# 4_-_DRIVERS.net
KiCad netlist of a schematic drawn in Altium Designer
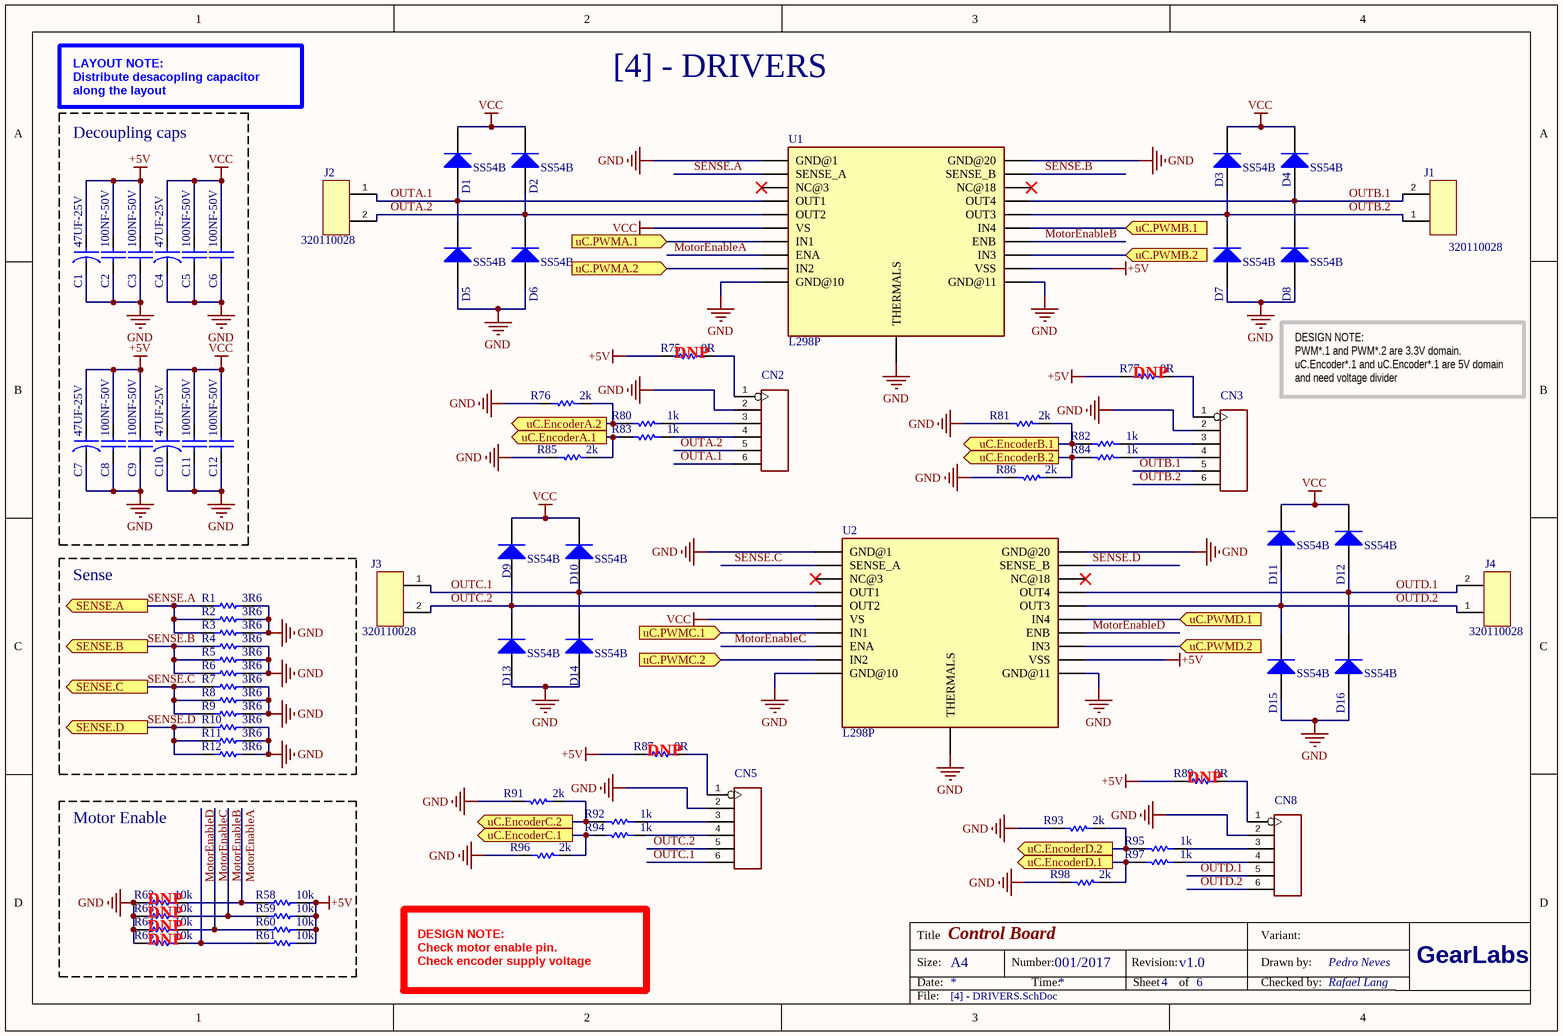
[diagram p0: [4] - DRIVERS.SchDoc]

(export (version "E")
  (design (tool "Eeschema 10.0.6"))
  (components
    (comp (ref "C1")
      (value "47UF-25V")
      (footprint "ELECTRO-SMD-C-6MM")
      (fields (field (name "MPN") "CS1E470M-CRE54") (field (name "Comment") "302030059"))
      (libsource (lib "Seeed-Capacitor") (part "ALUMINUM-SMD-47UF-25V(D6.3-H5.3MM)"))
    )
    (comp (ref "C2")
      (value "100NF-50V")
      (footprint "C0603")
      (fields (field (name "MPN") "CC0603KRX7R9BB104") (field (name "Comment") "302010138"))
      (libsource (lib "Seeed-Capacitor") (part "CERAMIC-100NF-50V-10%-X7R(0603)"))
    )
    (comp (ref "C3")
      (value "100NF-50V")
      (footprint "C0603")
      (fields (field (name "MPN") "CC0603KRX7R9BB104") (field (name "Comment") "302010138"))
      (libsource (lib "Seeed-Capacitor") (part "CERAMIC-100NF-50V-10%-X7R(0603)"))
    )
    (comp (ref "C4")
      (value "47UF-25V")
      (footprint "ELECTRO-SMD-C-6MM")
      (fields (field (name "MPN") "CS1E470M-CRE54") (field (name "Comment") "302030059"))
      (libsource (lib "Seeed-Capacitor") (part "ALUMINUM-SMD-47UF-25V(D6.3-H5.3MM)"))
    )
    (comp (ref "C5")
      (value "100NF-50V")
      (footprint "C0603")
      (fields (field (name "MPN") "CC0603KRX7R9BB104") (field (name "Comment") "302010138"))
      (libsource (lib "Seeed-Capacitor") (part "CERAMIC-100NF-50V-10%-X7R(0603)"))
    )
    (comp (ref "C6")
      (value "100NF-50V")
      (footprint "C0603")
      (fields (field (name "MPN") "CC0603KRX7R9BB104") (field (name "Comment") "302010138"))
      (libsource (lib "Seeed-Capacitor") (part "CERAMIC-100NF-50V-10%-X7R(0603)"))
    )
    (comp (ref "C7")
      (value "47UF-25V")
      (footprint "ELECTRO-SMD-C-6MM")
      (fields (field (name "MPN") "CS1E470M-CRE54") (field (name "Comment") "302030059"))
      (libsource (lib "Seeed-Capacitor") (part "ALUMINUM-SMD-47UF-25V(D6.3-H5.3MM)"))
    )
    (comp (ref "C8")
      (value "100NF-50V")
      (footprint "C0603")
      (fields (field (name "MPN") "CC0603KRX7R9BB104") (field (name "Comment") "302010138"))
      (libsource (lib "Seeed-Capacitor") (part "CERAMIC-100NF-50V-10%-X7R(0603)"))
    )
    (comp (ref "C9")
      (value "100NF-50V")
      (footprint "C0603")
      (fields (field (name "MPN") "CC0603KRX7R9BB104") (field (name "Comment") "302010138"))
      (libsource (lib "Seeed-Capacitor") (part "CERAMIC-100NF-50V-10%-X7R(0603)"))
    )
    (comp (ref "C10")
      (value "47UF-25V")
      (footprint "ELECTRO-SMD-C-6MM")
      (fields (field (name "MPN") "CS1E470M-CRE54") (field (name "Comment") "302030059"))
      (libsource (lib "Seeed-Capacitor") (part "ALUMINUM-SMD-47UF-25V(D6.3-H5.3MM)"))
    )
    (comp (ref "C11")
      (value "100NF-50V")
      (footprint "C0603")
      (fields (field (name "MPN") "CC0603KRX7R9BB104") (field (name "Comment") "302010138"))
      (libsource (lib "Seeed-Capacitor") (part "CERAMIC-100NF-50V-10%-X7R(0603)"))
    )
    (comp (ref "C12")
      (value "100NF-50V")
      (footprint "C0603")
      (fields (field (name "MPN") "CC0603KRX7R9BB104") (field (name "Comment") "302010138"))
      (libsource (lib "Seeed-Capacitor") (part "CERAMIC-100NF-50V-10%-X7R(0603)"))
    )
    (comp (ref "CN2")
      (value "320030060")
      (footprint "H6-2.54")
      (fields (field (name "MPN") "F185-1106A1BSYC1"))
      (libsource (lib "Seeed-Connector") (part "DIP-BLACK-FEMALE-HEADER-VERT(6P-2.54)"))
    )
    (comp (ref "CN3")
      (value "320030060")
      (footprint "H6-2.54")
      (fields (field (name "MPN") "F185-1106A1BSYC1"))
      (libsource (lib "Seeed-Connector") (part "DIP-BLACK-FEMALE-HEADER-VERT(6P-2.54)"))
    )
    (comp (ref "CN5")
      (value "320030060")
      (footprint "H6-2.54")
      (fields (field (name "MPN") "F185-1106A1BSYC1"))
      (libsource (lib "Seeed-Connector") (part "DIP-BLACK-FEMALE-HEADER-VERT(6P-2.54)"))
    )
    (comp (ref "CN8")
      (value "320030060")
      (footprint "H6-2.54")
      (fields (field (name "MPN") "F185-1106A1BSYC1"))
      (libsource (lib "Seeed-Connector") (part "DIP-BLACK-FEMALE-HEADER-VERT(6P-2.54)"))
    )
    (comp (ref "D1")
      (value "304020021")
      (footprint "DO-214AA")
      (fields (field (name "MPN") "SS54B"))
      (libsource (lib "Seeed-Diode") (part "SMD-DIODE-SCHOTTKY-28V-5A(DO-214AA)"))
    )
    (comp (ref "D2")
      (value "304020021")
      (footprint "DO-214AA")
      (fields (field (name "MPN") "SS54B"))
      (libsource (lib "Seeed-Diode") (part "SMD-DIODE-SCHOTTKY-28V-5A(DO-214AA)"))
    )
    (comp (ref "D3")
      (value "304020021")
      (footprint "DO-214AA")
      (fields (field (name "MPN") "SS54B"))
      (libsource (lib "Seeed-Diode") (part "SMD-DIODE-SCHOTTKY-28V-5A(DO-214AA)"))
    )
    (comp (ref "D4")
      (value "304020021")
      (footprint "DO-214AA")
      (fields (field (name "MPN") "SS54B"))
      (libsource (lib "Seeed-Diode") (part "SMD-DIODE-SCHOTTKY-28V-5A(DO-214AA)"))
    )
    (comp (ref "D5")
      (value "304020021")
      (footprint "DO-214AA")
      (fields (field (name "MPN") "SS54B"))
      (libsource (lib "Seeed-Diode") (part "SMD-DIODE-SCHOTTKY-28V-5A(DO-214AA)"))
    )
    (comp (ref "D6")
      (value "304020021")
      (footprint "DO-214AA")
      (fields (field (name "MPN") "SS54B"))
      (libsource (lib "Seeed-Diode") (part "SMD-DIODE-SCHOTTKY-28V-5A(DO-214AA)"))
    )
    (comp (ref "D7")
      (value "304020021")
      (footprint "DO-214AA")
      (fields (field (name "MPN") "SS54B"))
      (libsource (lib "Seeed-Diode") (part "SMD-DIODE-SCHOTTKY-28V-5A(DO-214AA)"))
    )
    (comp (ref "D8")
      (value "304020021")
      (footprint "DO-214AA")
      (fields (field (name "MPN") "SS54B"))
      (libsource (lib "Seeed-Diode") (part "SMD-DIODE-SCHOTTKY-28V-5A(DO-214AA)"))
    )
    (comp (ref "D9")
      (value "304020021")
      (footprint "DO-214AA")
      (fields (field (name "MPN") "SS54B"))
      (libsource (lib "Seeed-Diode") (part "SMD-DIODE-SCHOTTKY-28V-5A(DO-214AA)"))
    )
    (comp (ref "D10")
      (value "304020021")
      (footprint "DO-214AA")
      (fields (field (name "MPN") "SS54B"))
      (libsource (lib "Seeed-Diode") (part "SMD-DIODE-SCHOTTKY-28V-5A(DO-214AA)"))
    )
    (comp (ref "D11")
      (value "304020021")
      (footprint "DO-214AA")
      (fields (field (name "MPN") "SS54B"))
      (libsource (lib "Seeed-Diode") (part "SMD-DIODE-SCHOTTKY-28V-5A(DO-214AA)"))
    )
    (comp (ref "D12")
      (value "304020021")
      (footprint "DO-214AA")
      (fields (field (name "MPN") "SS54B"))
      (libsource (lib "Seeed-Diode") (part "SMD-DIODE-SCHOTTKY-28V-5A(DO-214AA)"))
    )
    (comp (ref "D13")
      (value "304020021")
      (footprint "DO-214AA")
      (fields (field (name "MPN") "SS54B"))
      (libsource (lib "Seeed-Diode") (part "SMD-DIODE-SCHOTTKY-28V-5A(DO-214AA)"))
    )
    (comp (ref "D14")
      (value "304020021")
      (footprint "DO-214AA")
      (fields (field (name "MPN") "SS54B"))
      (libsource (lib "Seeed-Diode") (part "SMD-DIODE-SCHOTTKY-28V-5A(DO-214AA)"))
    )
    (comp (ref "D15")
      (value "304020021")
      (footprint "DO-214AA")
      (fields (field (name "MPN") "SS54B"))
      (libsource (lib "Seeed-Diode") (part "SMD-DIODE-SCHOTTKY-28V-5A(DO-214AA)"))
    )
    (comp (ref "D16")
      (value "304020021")
      (footprint "DO-214AA")
      (fields (field (name "MPN") "SS54B"))
      (libsource (lib "Seeed-Diode") (part "SMD-DIODE-SCHOTTKY-28V-5A(DO-214AA)"))
    )
    (comp (ref "J1")
      (value "320110028")
      (footprint "H2-3.5-7.0X7.0MM")
      (libsource (lib "Seeed-Connector") (part "SCREW-TERMINAL-GREEN(2P-3.5) - BORNE"))
    )
    (comp (ref "J2")
      (value "320110028")
      (footprint "H2-3.5-7.0X7.0MM")
      (libsource (lib "") (part "SCREW-TERMINAL-GREEN(2P-3.5) - BORNE_1"))
    )
    (comp (ref "J3")
      (value "320110028")
      (footprint "H2-3.5-7.0X7.0MM")
      (libsource (lib "") (part "SCREW-TERMINAL-GREEN(2P-3.5) - BORNE_1"))
    )
    (comp (ref "J4")
      (value "320110028")
      (footprint "H2-3.5-7.0X7.0MM")
      (libsource (lib "Seeed-Connector") (part "SCREW-TERMINAL-GREEN(2P-3.5) - BORNE"))
    )
    (comp (ref "R1")
      (value "3R6")
      (footprint "R0603")
      (fields (field (name "MPN") "RC0603JR-073R6L") (field (name "Comment") "301010140"))
      (libsource (lib "Seeed-Resistor") (part "SMD-RES-3.6R-5%-1/10W(0603)"))
    )
    (comp (ref "R2")
      (value "3R6")
      (footprint "R0603")
      (fields (field (name "MPN") "RC0603JR-073R6L") (field (name "Comment") "301010140"))
      (libsource (lib "Seeed-Resistor") (part "SMD-RES-3.6R-5%-1/10W(0603)"))
    )
    (comp (ref "R3")
      (value "3R6")
      (footprint "R0603")
      (fields (field (name "MPN") "RC0603JR-073R6L") (field (name "Comment") "301010140"))
      (libsource (lib "Seeed-Resistor") (part "SMD-RES-3.6R-5%-1/10W(0603)"))
    )
    (comp (ref "R4")
      (value "3R6")
      (footprint "R0603")
      (fields (field (name "MPN") "RC0603JR-073R6L") (field (name "Comment") "301010140"))
      (libsource (lib "Seeed-Resistor") (part "SMD-RES-3.6R-5%-1/10W(0603)"))
    )
    (comp (ref "R5")
      (value "3R6")
      (footprint "R0603")
      (fields (field (name "MPN") "RC0603JR-073R6L") (field (name "Comment") "301010140"))
      (libsource (lib "Seeed-Resistor") (part "SMD-RES-3.6R-5%-1/10W(0603)"))
    )
    (comp (ref "R6")
      (value "3R6")
      (footprint "R0603")
      (fields (field (name "MPN") "RC0603JR-073R6L") (field (name "Comment") "301010140"))
      (libsource (lib "Seeed-Resistor") (part "SMD-RES-3.6R-5%-1/10W(0603)"))
    )
    (comp (ref "R7")
      (value "3R6")
      (footprint "R0603")
      (fields (field (name "MPN") "RC0603JR-073R6L") (field (name "Comment") "301010140"))
      (libsource (lib "Seeed-Resistor") (part "SMD-RES-3.6R-5%-1/10W(0603)"))
    )
    (comp (ref "R8")
      (value "3R6")
      (footprint "R0603")
      (fields (field (name "MPN") "RC0603JR-073R6L") (field (name "Comment") "301010140"))
      (libsource (lib "Seeed-Resistor") (part "SMD-RES-3.6R-5%-1/10W(0603)"))
    )
    (comp (ref "R9")
      (value "3R6")
      (footprint "R0603")
      (fields (field (name "MPN") "RC0603JR-073R6L") (field (name "Comment") "301010140"))
      (libsource (lib "Seeed-Resistor") (part "SMD-RES-3.6R-5%-1/10W(0603)"))
    )
    (comp (ref "R10")
      (value "3R6")
      (footprint "R0603")
      (fields (field (name "MPN") "RC0603JR-073R6L") (field (name "Comment") "301010140"))
      (libsource (lib "Seeed-Resistor") (part "SMD-RES-3.6R-5%-1/10W(0603)"))
    )
    (comp (ref "R11")
      (value "3R6")
      (footprint "R0603")
      (fields (field (name "MPN") "RC0603JR-073R6L") (field (name "Comment") "301010140"))
      (libsource (lib "Seeed-Resistor") (part "SMD-RES-3.6R-5%-1/10W(0603)"))
    )
    (comp (ref "R12")
      (value "3R6")
      (footprint "R0603")
      (fields (field (name "MPN") "RC0603JR-073R6L") (field (name "Comment") "301010140"))
      (libsource (lib "Seeed-Resistor") (part "SMD-RES-3.6R-5%-1/10W(0603)"))
    )
    (comp (ref "R58")
      (value "10k")
      (footprint "R0603")
      (fields (field (name "MPN") "RC0603JR-0710KL") (field (name "Comment") "301010293"))
      (libsource (lib "Seeed-Resistor") (part "SMD-RES-10K-5%-1/10W(0603)"))
    )
    (comp (ref "R59")
      (value "10k")
      (footprint "R0603")
      (fields (field (name "MPN") "RC0603JR-0710KL") (field (name "Comment") "301010293"))
      (libsource (lib "Seeed-Resistor") (part "SMD-RES-10K-5%-1/10W(0603)"))
    )
    (comp (ref "R60")
      (value "10k")
      (footprint "R0603")
      (fields (field (name "MPN") "RC0603JR-0710KL") (field (name "Comment") "301010293"))
      (libsource (lib "Seeed-Resistor") (part "SMD-RES-10K-5%-1/10W(0603)"))
    )
    (comp (ref "R61")
      (value "10k")
      (footprint "R0603")
      (fields (field (name "MPN") "RC0603JR-0710KL") (field (name "Comment") "301010293"))
      (libsource (lib "Seeed-Resistor") (part "SMD-RES-10K-5%-1/10W(0603)"))
    )
    (comp (ref "R62")
      (value "10k")
      (footprint "R0603")
      (fields (field (name "MPN") "RC0603JR-0710KL") (field (name "Comment") "301010293"))
      (libsource (lib "Seeed-Resistor") (part "SMD-RES-10K-5%-1/10W(0603)"))
    )
    (comp (ref "R63")
      (value "10k")
      (footprint "R0603")
      (fields (field (name "MPN") "RC0603JR-0710KL") (field (name "Comment") "301010293"))
      (libsource (lib "Seeed-Resistor") (part "SMD-RES-10K-5%-1/10W(0603)"))
    )
    (comp (ref "R64")
      (value "10k")
      (footprint "R0603")
      (fields (field (name "MPN") "RC0603JR-0710KL") (field (name "Comment") "301010293"))
      (libsource (lib "Seeed-Resistor") (part "SMD-RES-10K-5%-1/10W(0603)"))
    )
    (comp (ref "R65")
      (value "10k")
      (footprint "R0603")
      (fields (field (name "MPN") "RC0603JR-0710KL") (field (name "Comment") "301010293"))
      (libsource (lib "Seeed-Resistor") (part "SMD-RES-10K-5%-1/10W(0603)"))
    )
    (comp (ref "R75")
      (value "0R")
      (footprint "R0603")
      (fields (field (name "MPN") "RC0603JR-070RL") (field (name "Comment") "301010292"))
      (libsource (lib "Seeed-Resistor") (part "SMD-RES-0R-5%-1/10W(0603)"))
    )
    (comp (ref "R76")
      (value "2k")
      (footprint "R0603")
      (fields (field (name "MPN") "RC0603FR-072KL") (field (name "Comment") "301010221"))
      (libsource (lib "Seeed-Resistor") (part "SMD-RES-2K-1%-1/10W(0603)"))
    )
    (comp (ref "R77")
      (value "0R")
      (footprint "R0603")
      (fields (field (name "MPN") "RC0603JR-070RL") (field (name "Comment") "301010292"))
      (libsource (lib "Seeed-Resistor") (part "SMD-RES-0R-5%-1/10W(0603)"))
    )
    (comp (ref "R80")
      (value "1k")
      (footprint "R0603")
      (fields (field (name "MPN") "RC0603FR-071KL") (field (name "Comment") "301010298"))
      (libsource (lib "Seeed-Resistor") (part "SMD-RES-1K-1%-1/10W(0603)"))
    )
    (comp (ref "R81")
      (value "2k")
      (footprint "R0603")
      (fields (field (name "MPN") "RC0603FR-072KL") (field (name "Comment") "301010221"))
      (libsource (lib "Seeed-Resistor") (part "SMD-RES-2K-1%-1/10W(0603)"))
    )
    (comp (ref "R82")
      (value "1k")
      (footprint "R0603")
      (fields (field (name "MPN") "RC0603FR-071KL") (field (name "Comment") "301010298"))
      (libsource (lib "Seeed-Resistor") (part "SMD-RES-1K-1%-1/10W(0603)"))
    )
    (comp (ref "R83")
      (value "1k")
      (footprint "R0603")
      (fields (field (name "MPN") "RC0603FR-071KL") (field (name "Comment") "301010298"))
      (libsource (lib "Seeed-Resistor") (part "SMD-RES-1K-1%-1/10W(0603)"))
    )
    (comp (ref "R84")
      (value "1k")
      (footprint "R0603")
      (fields (field (name "MPN") "RC0603FR-071KL") (field (name "Comment") "301010298"))
      (libsource (lib "Seeed-Resistor") (part "SMD-RES-1K-1%-1/10W(0603)"))
    )
    (comp (ref "R85")
      (value "2k")
      (footprint "R0603")
      (fields (field (name "MPN") "RC0603FR-072KL") (field (name "Comment") "301010221"))
      (libsource (lib "Seeed-Resistor") (part "SMD-RES-2K-1%-1/10W(0603)"))
    )
    (comp (ref "R86")
      (value "2k")
      (footprint "R0603")
      (fields (field (name "MPN") "RC0603FR-072KL") (field (name "Comment") "301010221"))
      (libsource (lib "Seeed-Resistor") (part "SMD-RES-2K-1%-1/10W(0603)"))
    )
    (comp (ref "R87")
      (value "0R")
      (footprint "R0603")
      (fields (field (name "MPN") "RC0603JR-070RL") (field (name "Comment") "301010292"))
      (libsource (lib "Seeed-Resistor") (part "SMD-RES-0R-5%-1/10W(0603)"))
    )
    (comp (ref "R89")
      (value "0R")
      (footprint "R0603")
      (fields (field (name "MPN") "RC0603JR-070RL") (field (name "Comment") "301010292"))
      (libsource (lib "Seeed-Resistor") (part "SMD-RES-0R-5%-1/10W(0603)"))
    )
    (comp (ref "R91")
      (value "2k")
      (footprint "R0603")
      (fields (field (name "MPN") "RC0603FR-072KL") (field (name "Comment") "301010221"))
      (libsource (lib "Seeed-Resistor") (part "SMD-RES-2K-1%-1/10W(0603)"))
    )
    (comp (ref "R92")
      (value "1k")
      (footprint "R0603")
      (fields (field (name "MPN") "RC0603FR-071KL") (field (name "Comment") "301010298"))
      (libsource (lib "Seeed-Resistor") (part "SMD-RES-1K-1%-1/10W(0603)"))
    )
    (comp (ref "R93")
      (value "2k")
      (footprint "R0603")
      (fields (field (name "MPN") "RC0603FR-072KL") (field (name "Comment") "301010221"))
      (libsource (lib "Seeed-Resistor") (part "SMD-RES-2K-1%-1/10W(0603)"))
    )
    (comp (ref "R94")
      (value "1k")
      (footprint "R0603")
      (fields (field (name "MPN") "RC0603FR-071KL") (field (name "Comment") "301010298"))
      (libsource (lib "Seeed-Resistor") (part "SMD-RES-1K-1%-1/10W(0603)"))
    )
    (comp (ref "R95")
      (value "1k")
      (footprint "R0603")
      (fields (field (name "MPN") "RC0603FR-071KL") (field (name "Comment") "301010298"))
      (libsource (lib "Seeed-Resistor") (part "SMD-RES-1K-1%-1/10W(0603)"))
    )
    (comp (ref "R96")
      (value "2k")
      (footprint "R0603")
      (fields (field (name "MPN") "RC0603FR-072KL") (field (name "Comment") "301010221"))
      (libsource (lib "Seeed-Resistor") (part "SMD-RES-2K-1%-1/10W(0603)"))
    )
    (comp (ref "R97")
      (value "1k")
      (footprint "R0603")
      (fields (field (name "MPN") "RC0603FR-071KL") (field (name "Comment") "301010298"))
      (libsource (lib "Seeed-Resistor") (part "SMD-RES-1K-1%-1/10W(0603)"))
    )
    (comp (ref "R98")
      (value "2k")
      (footprint "R0603")
      (fields (field (name "MPN") "RC0603FR-072KL") (field (name "Comment") "301010221"))
      (libsource (lib "Seeed-Resistor") (part "SMD-RES-2K-1%-1/10W(0603)"))
    )
    (comp (ref "U1")
      (value "L298P")
      (footprint "SOIC20G-1.27-16X11MM")
      (libsource (lib "Seeed-IC") (part "DRIVER-L298P(SOIC20)"))
    )
    (comp (ref "U2")
      (value "L298P")
      (footprint "SOIC20G-1.27-16X11MM")
      (libsource (lib "Seeed-IC") (part "DRIVER-L298P(SOIC20)"))
    )
  )
  (nets
    (net (code "1") (name "+5V") (class "Default")
      (node (ref "C1") (pin "+") (pinfunction "+_+") (pintype "passive"))
      (node (ref "C2") (pin "1") (pinfunction "1_1") (pintype "passive"))
      (node (ref "C3") (pin "1") (pinfunction "1_1") (pintype "passive"))
      (node (ref "C7") (pin "+") (pinfunction "+_+") (pintype "passive"))
      (node (ref "C8") (pin "1") (pinfunction "1_1") (pintype "passive"))
      (node (ref "C9") (pin "1") (pinfunction "1_1") (pintype "passive"))
      (node (ref "R58") (pin "2") (pinfunction "2_2") (pintype "passive"))
      (node (ref "R59") (pin "2") (pinfunction "2_2") (pintype "passive"))
      (node (ref "R60") (pin "2") (pinfunction "2_2") (pintype "passive"))
      (node (ref "R61") (pin "2") (pinfunction "2_2") (pintype "passive"))
      (node (ref "R75") (pin "1") (pinfunction "1_1") (pintype "passive"))
      (node (ref "R77") (pin "1") (pinfunction "1_1") (pintype "passive"))
      (node (ref "R87") (pin "1") (pinfunction "1_1") (pintype "passive"))
      (node (ref "R89") (pin "1") (pinfunction "1_1") (pintype "passive"))
      (node (ref "U1") (pin "12") (pinfunction "VSS_12") (pintype "passive"))
      (node (ref "U2") (pin "12") (pinfunction "VSS_12") (pintype "passive"))
    )
    (net (code "2") (name "/MotorEnableA") (class "Default")
      (node (ref "R58") (pin "1") (pinfunction "1_1") (pintype "passive"))
      (node (ref "R62") (pin "2") (pinfunction "2_2") (pintype "passive"))
      (node (ref "U1") (pin "8") (pinfunction "ENA_8") (pintype "passive"))
    )
    (net (code "3") (name "/MotorEnableB") (class "Default")
      (node (ref "R59") (pin "1") (pinfunction "1_1") (pintype "passive"))
      (node (ref "R63") (pin "2") (pinfunction "2_2") (pintype "passive"))
      (node (ref "U1") (pin "14") (pinfunction "ENB_14") (pintype "passive"))
    )
    (net (code "4") (name "/MotorEnableC") (class "Default")
      (node (ref "R60") (pin "1") (pinfunction "1_1") (pintype "passive"))
      (node (ref "R64") (pin "2") (pinfunction "2_2") (pintype "passive"))
      (node (ref "U2") (pin "8") (pinfunction "ENA_8") (pintype "passive"))
    )
    (net (code "5") (name "/MotorEnableD") (class "Default")
      (node (ref "R61") (pin "1") (pinfunction "1_1") (pintype "passive"))
      (node (ref "R65") (pin "2") (pinfunction "2_2") (pintype "passive"))
      (node (ref "U2") (pin "14") (pinfunction "ENB_14") (pintype "passive"))
    )
    (net (code "6") (name "/OUTA.1") (class "Default")
      (node (ref "CN2") (pin "6") (pinfunction "6_6") (pintype "passive"))
      (node (ref "D1") (pin "+") (pinfunction "+_+") (pintype "passive"))
      (node (ref "D5") (pin "-") (pinfunction "-_-") (pintype "passive"))
      (node (ref "J2") (pin "1") (pinfunction "1_1") (pintype "passive"))
      (node (ref "U1") (pin "4") (pinfunction "OUT1_4") (pintype "passive"))
    )
    (net (code "7") (name "/OUTA.2") (class "Default")
      (node (ref "CN2") (pin "5") (pinfunction "5_5") (pintype "passive"))
      (node (ref "D2") (pin "+") (pinfunction "+_+") (pintype "passive"))
      (node (ref "D6") (pin "-") (pinfunction "-_-") (pintype "passive"))
      (node (ref "J2") (pin "2") (pinfunction "2_2") (pintype "passive"))
      (node (ref "U1") (pin "5") (pinfunction "OUT2_5") (pintype "passive"))
    )
    (net (code "8") (name "/OUTB.1") (class "Default")
      (node (ref "CN3") (pin "5") (pinfunction "5_5") (pintype "passive"))
      (node (ref "D4") (pin "+") (pinfunction "+_+") (pintype "passive"))
      (node (ref "D8") (pin "-") (pinfunction "-_-") (pintype "passive"))
      (node (ref "J1") (pin "2") (pinfunction "2_2") (pintype "passive"))
      (node (ref "U1") (pin "17") (pinfunction "OUT4_17") (pintype "passive"))
    )
    (net (code "9") (name "/OUTB.2") (class "Default")
      (node (ref "CN3") (pin "6") (pinfunction "6_6") (pintype "passive"))
      (node (ref "D3") (pin "+") (pinfunction "+_+") (pintype "passive"))
      (node (ref "D7") (pin "-") (pinfunction "-_-") (pintype "passive"))
      (node (ref "J1") (pin "1") (pinfunction "1_1") (pintype "passive"))
      (node (ref "U1") (pin "16") (pinfunction "OUT3_16") (pintype "passive"))
    )
    (net (code "10") (name "/OUTC.1") (class "Default")
      (node (ref "CN5") (pin "6") (pinfunction "6_6") (pintype "passive"))
      (node (ref "D10") (pin "+") (pinfunction "+_+") (pintype "passive"))
      (node (ref "D14") (pin "-") (pinfunction "-_-") (pintype "passive"))
      (node (ref "J3") (pin "1") (pinfunction "1_1") (pintype "passive"))
      (node (ref "U2") (pin "4") (pinfunction "OUT1_4") (pintype "passive"))
    )
    (net (code "11") (name "/OUTC.2") (class "Default")
      (node (ref "CN5") (pin "5") (pinfunction "5_5") (pintype "passive"))
      (node (ref "D13") (pin "-") (pinfunction "-_-") (pintype "passive"))
      (node (ref "D9") (pin "+") (pinfunction "+_+") (pintype "passive"))
      (node (ref "J3") (pin "2") (pinfunction "2_2") (pintype "passive"))
      (node (ref "U2") (pin "5") (pinfunction "OUT2_5") (pintype "passive"))
    )
    (net (code "12") (name "/OUTD.1") (class "Default")
      (node (ref "CN8") (pin "5") (pinfunction "5_5") (pintype "passive"))
      (node (ref "D12") (pin "+") (pinfunction "+_+") (pintype "passive"))
      (node (ref "D16") (pin "-") (pinfunction "-_-") (pintype "passive"))
      (node (ref "J4") (pin "2") (pinfunction "2_2") (pintype "passive"))
      (node (ref "U2") (pin "17") (pinfunction "OUT4_17") (pintype "passive"))
    )
    (net (code "13") (name "/OUTD.2") (class "Default")
      (node (ref "CN8") (pin "6") (pinfunction "6_6") (pintype "passive"))
      (node (ref "D11") (pin "+") (pinfunction "+_+") (pintype "passive"))
      (node (ref "D15") (pin "-") (pinfunction "-_-") (pintype "passive"))
      (node (ref "J4") (pin "1") (pinfunction "1_1") (pintype "passive"))
      (node (ref "U2") (pin "16") (pinfunction "OUT3_16") (pintype "passive"))
    )
    (net (code "14") (name "/SENSE.A") (class "Default")
      (node (ref "R1") (pin "1") (pinfunction "1_1") (pintype "passive"))
      (node (ref "R2") (pin "1") (pinfunction "1_1") (pintype "passive"))
      (node (ref "R3") (pin "1") (pinfunction "1_1") (pintype "passive"))
      (node (ref "U1") (pin "2") (pinfunction "SENSE_A_2") (pintype "passive"))
    )
    (net (code "15") (name "/SENSE.B") (class "Default")
      (node (ref "R4") (pin "1") (pinfunction "1_1") (pintype "passive"))
      (node (ref "R5") (pin "1") (pinfunction "1_1") (pintype "passive"))
      (node (ref "R6") (pin "1") (pinfunction "1_1") (pintype "passive"))
      (node (ref "U1") (pin "19") (pinfunction "SENSE_B_19") (pintype "passive"))
    )
    (net (code "16") (name "/SENSE.C") (class "Default")
      (node (ref "R7") (pin "1") (pinfunction "1_1") (pintype "passive"))
      (node (ref "R8") (pin "1") (pinfunction "1_1") (pintype "passive"))
      (node (ref "R9") (pin "1") (pinfunction "1_1") (pintype "passive"))
      (node (ref "U2") (pin "2") (pinfunction "SENSE_A_2") (pintype "passive"))
    )
    (net (code "17") (name "/SENSE.D") (class "Default")
      (node (ref "R10") (pin "1") (pinfunction "1_1") (pintype "passive"))
      (node (ref "R11") (pin "1") (pinfunction "1_1") (pintype "passive"))
      (node (ref "R12") (pin "1") (pinfunction "1_1") (pintype "passive"))
      (node (ref "U2") (pin "19") (pinfunction "SENSE_B_19") (pintype "passive"))
    )
    (net (code "18") (name "/uC.EncoderA.1") (class "Default")
      (node (ref "R83") (pin "2") (pinfunction "2_2") (pintype "passive"))
      (node (ref "R85") (pin "2") (pinfunction "2_2") (pintype "passive"))
    )
    (net (code "19") (name "/uC.EncoderA.2") (class "Default")
      (node (ref "R76") (pin "2") (pinfunction "2_2") (pintype "passive"))
      (node (ref "R80") (pin "2") (pinfunction "2_2") (pintype "passive"))
    )
    (net (code "20") (name "/uC.EncoderB.1") (class "Default")
      (node (ref "R81") (pin "2") (pinfunction "2_2") (pintype "passive"))
      (node (ref "R82") (pin "2") (pinfunction "2_2") (pintype "passive"))
    )
    (net (code "21") (name "/uC.EncoderB.2") (class "Default")
      (node (ref "R84") (pin "2") (pinfunction "2_2") (pintype "passive"))
      (node (ref "R86") (pin "2") (pinfunction "2_2") (pintype "passive"))
    )
    (net (code "22") (name "/uC.EncoderC.1") (class "Default")
      (node (ref "R94") (pin "2") (pinfunction "2_2") (pintype "passive"))
      (node (ref "R96") (pin "2") (pinfunction "2_2") (pintype "passive"))
    )
    (net (code "23") (name "/uC.EncoderC.2") (class "Default")
      (node (ref "R91") (pin "2") (pinfunction "2_2") (pintype "passive"))
      (node (ref "R92") (pin "2") (pinfunction "2_2") (pintype "passive"))
    )
    (net (code "24") (name "/uC.EncoderD.1") (class "Default")
      (node (ref "R97") (pin "2") (pinfunction "2_2") (pintype "passive"))
      (node (ref "R98") (pin "2") (pinfunction "2_2") (pintype "passive"))
    )
    (net (code "25") (name "/uC.EncoderD.2") (class "Default")
      (node (ref "R93") (pin "2") (pinfunction "2_2") (pintype "passive"))
      (node (ref "R95") (pin "2") (pinfunction "2_2") (pintype "passive"))
    )
    (net (code "26") (name "/uC.PWMA.1") (class "Default")
      (node (ref "U1") (pin "7") (pinfunction "IN1_7") (pintype "passive"))
    )
    (net (code "27") (name "/uC.PWMA.2") (class "Default")
      (node (ref "U1") (pin "9") (pinfunction "IN2_9") (pintype "passive"))
    )
    (net (code "28") (name "/uC.PWMB.1") (class "Default")
      (node (ref "U1") (pin "15") (pinfunction "IN4_15") (pintype "passive"))
    )
    (net (code "29") (name "/uC.PWMB.2") (class "Default")
      (node (ref "U1") (pin "13") (pinfunction "IN3_13") (pintype "passive"))
    )
    (net (code "30") (name "/uC.PWMC.1") (class "Default")
      (node (ref "U2") (pin "7") (pinfunction "IN1_7") (pintype "passive"))
    )
    (net (code "31") (name "/uC.PWMC.2") (class "Default")
      (node (ref "U2") (pin "9") (pinfunction "IN2_9") (pintype "passive"))
    )
    (net (code "32") (name "/uC.PWMD.1") (class "Default")
      (node (ref "U2") (pin "15") (pinfunction "IN4_15") (pintype "passive"))
    )
    (net (code "33") (name "/uC.PWMD.2") (class "Default")
      (node (ref "U2") (pin "13") (pinfunction "IN3_13") (pintype "passive"))
    )
    (net (code "34") (name "GND") (class "Default")
      (node (ref "C1") (pin "-") (pinfunction "-_-") (pintype "passive"))
      (node (ref "C10") (pin "-") (pinfunction "-_-") (pintype "passive"))
      (node (ref "C11") (pin "2") (pinfunction "2_2") (pintype "passive"))
      (node (ref "C12") (pin "2") (pinfunction "2_2") (pintype "passive"))
      (node (ref "C2") (pin "2") (pinfunction "2_2") (pintype "passive"))
      (node (ref "C3") (pin "2") (pinfunction "2_2") (pintype "passive"))
      (node (ref "C4") (pin "-") (pinfunction "-_-") (pintype "passive"))
      (node (ref "C5") (pin "2") (pinfunction "2_2") (pintype "passive"))
      (node (ref "C6") (pin "2") (pinfunction "2_2") (pintype "passive"))
      (node (ref "C7") (pin "-") (pinfunction "-_-") (pintype "passive"))
      (node (ref "C8") (pin "2") (pinfunction "2_2") (pintype "passive"))
      (node (ref "C9") (pin "2") (pinfunction "2_2") (pintype "passive"))
      (node (ref "CN2") (pin "2") (pinfunction "2_2") (pintype "passive"))
      (node (ref "CN3") (pin "2") (pinfunction "2_2") (pintype "passive"))
      (node (ref "CN5") (pin "2") (pinfunction "2_2") (pintype "passive"))
      (node (ref "CN8") (pin "2") (pinfunction "2_2") (pintype "passive"))
      (node (ref "D13") (pin "+") (pinfunction "+_+") (pintype "passive"))
      (node (ref "D14") (pin "+") (pinfunction "+_+") (pintype "passive"))
      (node (ref "D15") (pin "+") (pinfunction "+_+") (pintype "passive"))
      (node (ref "D16") (pin "+") (pinfunction "+_+") (pintype "passive"))
      (node (ref "D5") (pin "+") (pinfunction "+_+") (pintype "passive"))
      (node (ref "D6") (pin "+") (pinfunction "+_+") (pintype "passive"))
      (node (ref "D7") (pin "+") (pinfunction "+_+") (pintype "passive"))
      (node (ref "D8") (pin "+") (pinfunction "+_+") (pintype "passive"))
      (node (ref "R1") (pin "2") (pinfunction "2_2") (pintype "passive"))
      (node (ref "R10") (pin "2") (pinfunction "2_2") (pintype "passive"))
      (node (ref "R11") (pin "2") (pinfunction "2_2") (pintype "passive"))
      (node (ref "R12") (pin "2") (pinfunction "2_2") (pintype "passive"))
      (node (ref "R2") (pin "2") (pinfunction "2_2") (pintype "passive"))
      (node (ref "R3") (pin "2") (pinfunction "2_2") (pintype "passive"))
      (node (ref "R4") (pin "2") (pinfunction "2_2") (pintype "passive"))
      (node (ref "R5") (pin "2") (pinfunction "2_2") (pintype "passive"))
      (node (ref "R6") (pin "2") (pinfunction "2_2") (pintype "passive"))
      (node (ref "R62") (pin "1") (pinfunction "1_1") (pintype "passive"))
      (node (ref "R63") (pin "1") (pinfunction "1_1") (pintype "passive"))
      (node (ref "R64") (pin "1") (pinfunction "1_1") (pintype "passive"))
      (node (ref "R65") (pin "1") (pinfunction "1_1") (pintype "passive"))
      (node (ref "R7") (pin "2") (pinfunction "2_2") (pintype "passive"))
      (node (ref "R76") (pin "1") (pinfunction "1_1") (pintype "passive"))
      (node (ref "R8") (pin "2") (pinfunction "2_2") (pintype "passive"))
      (node (ref "R81") (pin "1") (pinfunction "1_1") (pintype "passive"))
      (node (ref "R85") (pin "1") (pinfunction "1_1") (pintype "passive"))
      (node (ref "R86") (pin "1") (pinfunction "1_1") (pintype "passive"))
      (node (ref "R9") (pin "2") (pinfunction "2_2") (pintype "passive"))
      (node (ref "R91") (pin "1") (pinfunction "1_1") (pintype "passive"))
      (node (ref "R93") (pin "1") (pinfunction "1_1") (pintype "passive"))
      (node (ref "R96") (pin "1") (pinfunction "1_1") (pintype "passive"))
      (node (ref "R98") (pin "1") (pinfunction "1_1") (pintype "passive"))
      (node (ref "U1") (pin "1") (pinfunction "GND@1_1") (pintype "passive"))
      (node (ref "U1") (pin "10") (pinfunction "GND@10_10") (pintype "passive"))
      (node (ref "U1") (pin "11") (pinfunction "GND@11_11") (pintype "passive"))
      (node (ref "U1") (pin "20") (pinfunction "GND@20_20") (pintype "passive"))
      (node (ref "U1") (pin "THERMALS") (pinfunction "THERMALS_THERMALS") (pintype "passive"))
      (node (ref "U2") (pin "1") (pinfunction "GND@1_1") (pintype "passive"))
      (node (ref "U2") (pin "10") (pinfunction "GND@10_10") (pintype "passive"))
      (node (ref "U2") (pin "11") (pinfunction "GND@11_11") (pintype "passive"))
      (node (ref "U2") (pin "20") (pinfunction "GND@20_20") (pintype "passive"))
      (node (ref "U2") (pin "THERMALS") (pinfunction "THERMALS_THERMALS") (pintype "passive"))
    )
    (net (code "35") (name "Net-(CN2-Pad1)") (class "Default")
      (node (ref "CN2") (pin "1") (pinfunction "1_1") (pintype "passive"))
      (node (ref "R75") (pin "2") (pinfunction "2_2") (pintype "passive"))
    )
    (net (code "36") (name "Net-(CN2-Pad3)") (class "Default")
      (node (ref "CN2") (pin "3") (pinfunction "3_3") (pintype "passive"))
      (node (ref "R80") (pin "1") (pinfunction "1_1") (pintype "passive"))
    )
    (net (code "37") (name "Net-(CN2-Pad4)") (class "Default")
      (node (ref "CN2") (pin "4") (pinfunction "4_4") (pintype "passive"))
      (node (ref "R83") (pin "1") (pinfunction "1_1") (pintype "passive"))
    )
    (net (code "38") (name "Net-(CN3-Pad1)") (class "Default")
      (node (ref "CN3") (pin "1") (pinfunction "1_1") (pintype "passive"))
      (node (ref "R77") (pin "2") (pinfunction "2_2") (pintype "passive"))
    )
    (net (code "39") (name "Net-(CN3-Pad3)") (class "Default")
      (node (ref "CN3") (pin "3") (pinfunction "3_3") (pintype "passive"))
      (node (ref "R82") (pin "1") (pinfunction "1_1") (pintype "passive"))
    )
    (net (code "40") (name "Net-(CN3-Pad4)") (class "Default")
      (node (ref "CN3") (pin "4") (pinfunction "4_4") (pintype "passive"))
      (node (ref "R84") (pin "1") (pinfunction "1_1") (pintype "passive"))
    )
    (net (code "41") (name "Net-(CN5-Pad1)") (class "Default")
      (node (ref "CN5") (pin "1") (pinfunction "1_1") (pintype "passive"))
      (node (ref "R87") (pin "2") (pinfunction "2_2") (pintype "passive"))
    )
    (net (code "42") (name "Net-(CN5-Pad3)") (class "Default")
      (node (ref "CN5") (pin "3") (pinfunction "3_3") (pintype "passive"))
      (node (ref "R92") (pin "1") (pinfunction "1_1") (pintype "passive"))
    )
    (net (code "43") (name "Net-(CN5-Pad4)") (class "Default")
      (node (ref "CN5") (pin "4") (pinfunction "4_4") (pintype "passive"))
      (node (ref "R94") (pin "1") (pinfunction "1_1") (pintype "passive"))
    )
    (net (code "44") (name "Net-(CN8-Pad1)") (class "Default")
      (node (ref "CN8") (pin "1") (pinfunction "1_1") (pintype "passive"))
      (node (ref "R89") (pin "2") (pinfunction "2_2") (pintype "passive"))
    )
    (net (code "45") (name "Net-(CN8-Pad3)") (class "Default")
      (node (ref "CN8") (pin "3") (pinfunction "3_3") (pintype "passive"))
      (node (ref "R95") (pin "1") (pinfunction "1_1") (pintype "passive"))
    )
    (net (code "46") (name "Net-(CN8-Pad4)") (class "Default")
      (node (ref "CN8") (pin "4") (pinfunction "4_4") (pintype "passive"))
      (node (ref "R97") (pin "1") (pinfunction "1_1") (pintype "passive"))
    )
    (net (code "47") (name "VCC") (class "Default")
      (node (ref "C10") (pin "+") (pinfunction "+_+") (pintype "passive"))
      (node (ref "C11") (pin "1") (pinfunction "1_1") (pintype "passive"))
      (node (ref "C12") (pin "1") (pinfunction "1_1") (pintype "passive"))
      (node (ref "C4") (pin "+") (pinfunction "+_+") (pintype "passive"))
      (node (ref "C5") (pin "1") (pinfunction "1_1") (pintype "passive"))
      (node (ref "C6") (pin "1") (pinfunction "1_1") (pintype "passive"))
      (node (ref "D1") (pin "-") (pinfunction "-_-") (pintype "passive"))
      (node (ref "D10") (pin "-") (pinfunction "-_-") (pintype "passive"))
      (node (ref "D11") (pin "-") (pinfunction "-_-") (pintype "passive"))
      (node (ref "D12") (pin "-") (pinfunction "-_-") (pintype "passive"))
      (node (ref "D2") (pin "-") (pinfunction "-_-") (pintype "passive"))
      (node (ref "D3") (pin "-") (pinfunction "-_-") (pintype "passive"))
      (node (ref "D4") (pin "-") (pinfunction "-_-") (pintype "passive"))
      (node (ref "D9") (pin "-") (pinfunction "-_-") (pintype "passive"))
      (node (ref "U1") (pin "6") (pinfunction "VS_6") (pintype "passive"))
      (node (ref "U2") (pin "6") (pinfunction "VS_6") (pintype "passive"))
    )
    (net (code "48") (name "unconnected-(U1-NC@3-Pad3)") (class "Default")
      (node (ref "U1") (pin "3") (pinfunction "NC@3_3") (pintype "passive+no_connect"))
    )
    (net (code "49") (name "unconnected-(U1-NC@18-Pad18)") (class "Default")
      (node (ref "U1") (pin "18") (pinfunction "NC@18_18") (pintype "passive+no_connect"))
    )
    (net (code "50") (name "unconnected-(U2-NC@3-Pad3)") (class "Default")
      (node (ref "U2") (pin "3") (pinfunction "NC@3_3") (pintype "passive+no_connect"))
    )
    (net (code "51") (name "unconnected-(U2-NC@18-Pad18)") (class "Default")
      (node (ref "U2") (pin "18") (pinfunction "NC@18_18") (pintype "passive+no_connect"))
    )
  )
)
